# schematic.net
KiCad netlist of a schematic drawn in EasyEDA
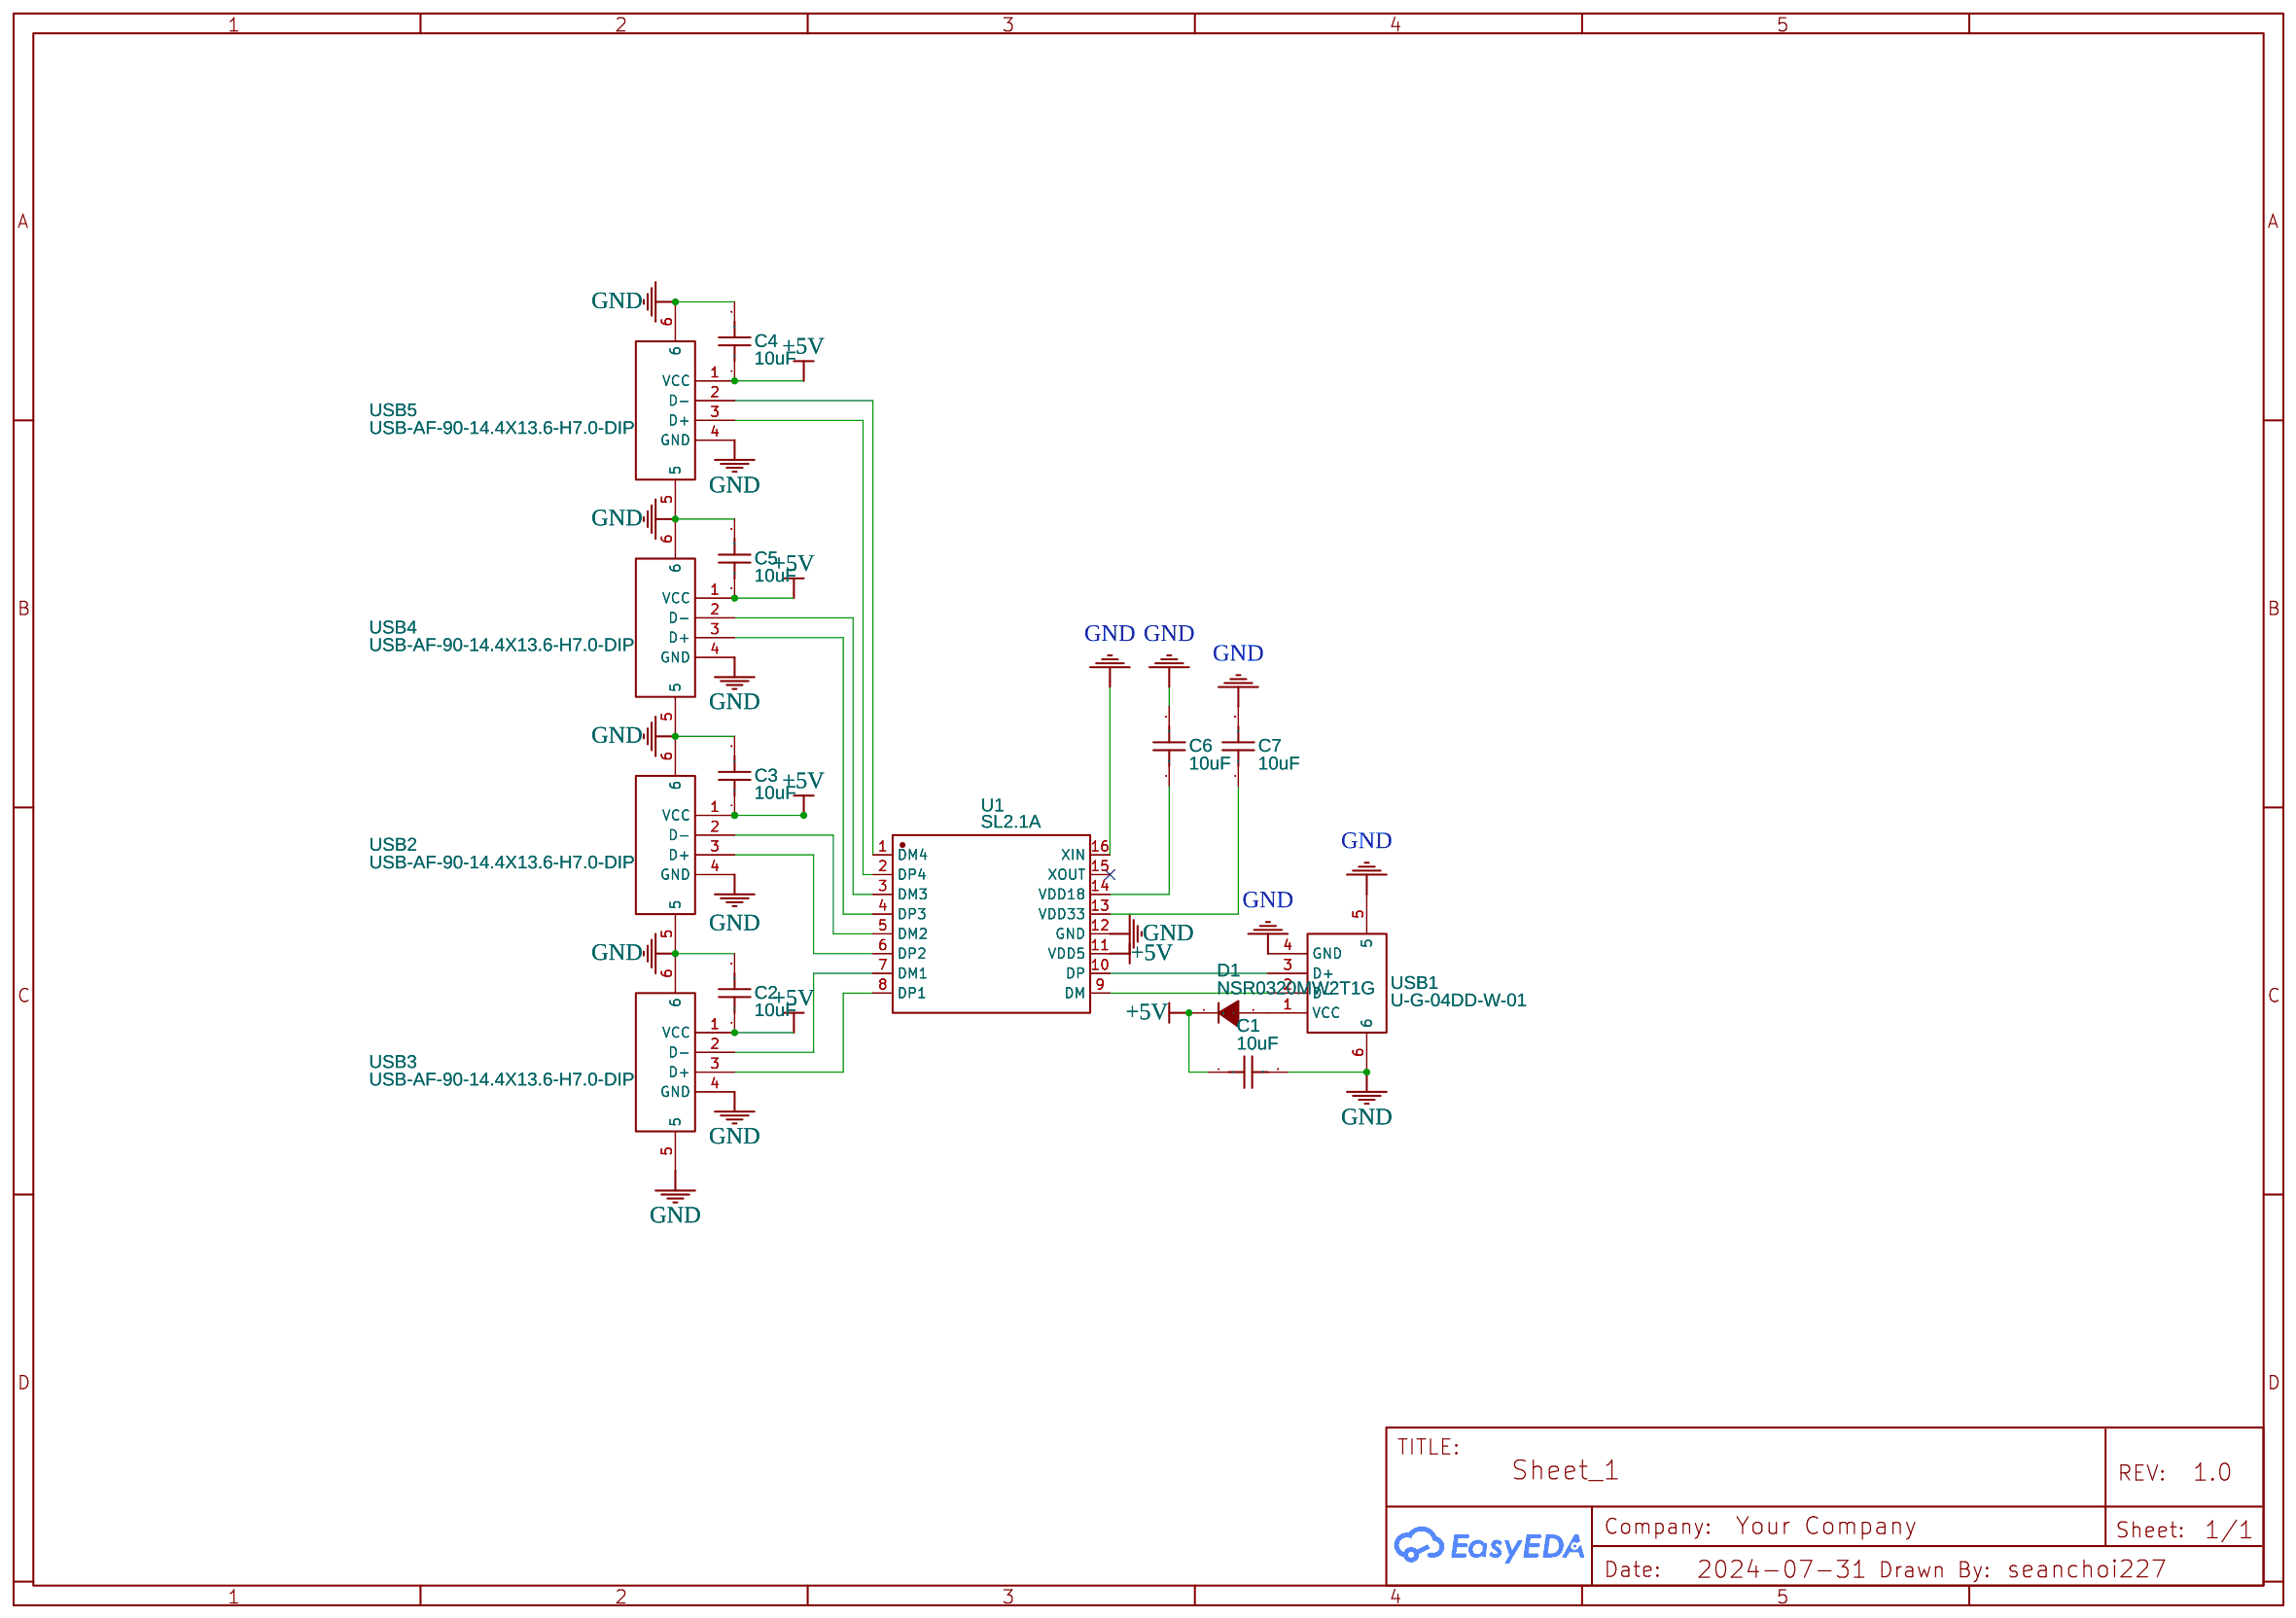
[diagram p0: schematic sheet]

(export (version "E")
  (design (tool "Eeschema 10.0.6"))
  (components
    (comp (ref "C1")
      (value "10uF")
      (fields
        (field (name "Manufacturer Part") "CL10A106KP8NNNC")
        (field (name "Manufacturer") "SAMSUNG(三星)")
      )
      (libsource (lib "") (part "CL10A106KP8NNNC_1"))
    )
    (comp (ref "C2")
      (value "10uF")
      (fields
        (field (name "Manufacturer Part") "CL10A106KP8NNNC")
        (field (name "Manufacturer") "SAMSUNG(三星)")
      )
      (libsource (lib "") (part "CL10A106KP8NNNC"))
    )
    (comp (ref "C3")
      (value "10uF")
      (fields
        (field (name "Manufacturer Part") "CL10A106KP8NNNC")
        (field (name "Manufacturer") "SAMSUNG(三星)")
      )
      (libsource (lib "") (part "CL10A106KP8NNNC"))
    )
    (comp (ref "C4")
      (value "10uF")
      (fields
        (field (name "Manufacturer Part") "CL10A106KP8NNNC")
        (field (name "Manufacturer") "SAMSUNG(三星)")
      )
      (libsource (lib "") (part "CL10A106KP8NNNC"))
    )
    (comp (ref "C5")
      (value "10uF")
      (fields
        (field (name "Manufacturer Part") "CL10A106KP8NNNC")
        (field (name "Manufacturer") "SAMSUNG(三星)")
      )
      (libsource (lib "") (part "CL10A106KP8NNNC"))
    )
    (comp (ref "C6")
      (value "10uF")
      (fields
        (field (name "Manufacturer Part") "CL10A106KP8NNNC")
        (field (name "Manufacturer") "SAMSUNG(三星)")
      )
      (libsource (lib "") (part "CL10A106KP8NNNC"))
    )
    (comp (ref "C7")
      (value "10uF")
      (fields
        (field (name "Manufacturer Part") "CL10A106KP8NNNC")
        (field (name "Manufacturer") "SAMSUNG(三星)")
      )
      (libsource (lib "") (part "CL10A106KP8NNNC"))
    )
    (comp (ref "D1")
      (value "NSR0320MW2T1G")
      (fields (field (name "Manufacturer") "onsemi(安森美)"))
      (libsource (lib "") (part "NSR0320MW2T1G"))
    )
    (comp (ref "U1")
      (value "SL2.1A")
      (fields (field (name "Manufacturer") "CoreChips(和芯润德)"))
      (libsource (lib "") (part "SL2.1A"))
    )
    (comp (ref "USB1")
      (value "U-G-04DD-W-01")
      (fields (field (name "Manufacturer Part") "U-G-O4DD-W-1") (field (name "Manufacturer") "韩国韩荣"))
      (libsource (lib "") (part "U-G-04DD-W-01"))
    )
    (comp (ref "USB2")
      (value "USB-AF-90-14.4X13.6-H7.0-DIP")
      (fields (field (name "Manufacturer Part") "903-131A1011D10100") (field (name "Manufacturer") "精拓金"))
      (libsource (lib "") (part "USB-AF-90-14.4X13.6-H7.0-DIP"))
    )
    (comp (ref "USB3")
      (value "USB-AF-90-14.4X13.6-H7.0-DIP")
      (fields (field (name "Manufacturer Part") "903-131A1011D10100") (field (name "Manufacturer") "精拓金"))
      (libsource (lib "") (part "USB-AF-90-14.4X13.6-H7.0-DIP"))
    )
    (comp (ref "USB4")
      (value "USB-AF-90-14.4X13.6-H7.0-DIP")
      (fields (field (name "Manufacturer Part") "903-131A1011D10100") (field (name "Manufacturer") "精拓金"))
      (libsource (lib "") (part "USB-AF-90-14.4X13.6-H7.0-DIP"))
    )
    (comp (ref "USB5")
      (value "USB-AF-90-14.4X13.6-H7.0-DIP")
      (fields (field (name "Manufacturer Part") "903-131A1011D10100") (field (name "Manufacturer") "精拓金"))
      (libsource (lib "") (part "USB-AF-90-14.4X13.6-H7.0-DIP"))
    )
  )
  (nets
    (net (code "1") (name "+5V") (class "Default")
      (node (ref "C1") (pin "1") (pinfunction "1_1") (pintype "unspecified"))
      (node (ref "C2") (pin "1") (pinfunction "1_1") (pintype "unspecified"))
      (node (ref "C3") (pin "1") (pinfunction "1_1") (pintype "unspecified"))
      (node (ref "C4") (pin "1") (pinfunction "1_1") (pintype "unspecified"))
      (node (ref "C5") (pin "1") (pinfunction "1_1") (pintype "unspecified"))
      (node (ref "D1") (pin "1") (pinfunction "C_1") (pintype "unspecified"))
      (node (ref "U1") (pin "11") (pinfunction "VDD5_11") (pintype "unspecified"))
      (node (ref "USB2") (pin "1") (pinfunction "VCC_1") (pintype "unspecified"))
      (node (ref "USB3") (pin "1") (pinfunction "VCC_1") (pintype "unspecified"))
      (node (ref "USB4") (pin "1") (pinfunction "VCC_1") (pintype "unspecified"))
      (node (ref "USB5") (pin "1") (pinfunction "VCC_1") (pintype "unspecified"))
    )
    (net (code "2") (name "GND") (class "Default")
      (node (ref "C1") (pin "2") (pinfunction "2_2") (pintype "unspecified"))
      (node (ref "C2") (pin "2") (pinfunction "2_2") (pintype "unspecified"))
      (node (ref "C3") (pin "2") (pinfunction "2_2") (pintype "unspecified"))
      (node (ref "C4") (pin "2") (pinfunction "2_2") (pintype "unspecified"))
      (node (ref "C5") (pin "2") (pinfunction "2_2") (pintype "unspecified"))
      (node (ref "C6") (pin "2") (pinfunction "2_2") (pintype "unspecified"))
      (node (ref "C7") (pin "2") (pinfunction "2_2") (pintype "unspecified"))
      (node (ref "U1") (pin "12") (pinfunction "GND_12") (pintype "unspecified"))
      (node (ref "U1") (pin "16") (pinfunction "XIN_16") (pintype "unspecified"))
      (node (ref "USB1") (pin "4") (pinfunction "GND_4") (pintype "unspecified"))
      (node (ref "USB1") (pin "5") (pinfunction "5_5") (pintype "unspecified"))
      (node (ref "USB1") (pin "6") (pinfunction "6_6") (pintype "unspecified"))
      (node (ref "USB2") (pin "4") (pinfunction "GND_4") (pintype "unspecified"))
      (node (ref "USB2") (pin "5") (pinfunction "5_5") (pintype "unspecified"))
      (node (ref "USB2") (pin "6") (pinfunction "6_6") (pintype "unspecified"))
      (node (ref "USB3") (pin "4") (pinfunction "GND_4") (pintype "unspecified"))
      (node (ref "USB3") (pin "5") (pinfunction "5_5") (pintype "unspecified"))
      (node (ref "USB3") (pin "6") (pinfunction "6_6") (pintype "unspecified"))
      (node (ref "USB4") (pin "4") (pinfunction "GND_4") (pintype "unspecified"))
      (node (ref "USB4") (pin "5") (pinfunction "5_5") (pintype "unspecified"))
      (node (ref "USB4") (pin "6") (pinfunction "6_6") (pintype "unspecified"))
      (node (ref "USB5") (pin "4") (pinfunction "GND_4") (pintype "unspecified"))
      (node (ref "USB5") (pin "5") (pinfunction "5_5") (pintype "unspecified"))
      (node (ref "USB5") (pin "6") (pinfunction "6_6") (pintype "unspecified"))
    )
    (net (code "3") (name "Net-(D1-A)") (class "Default")
      (node (ref "D1") (pin "2") (pinfunction "A_2") (pintype "unspecified"))
      (node (ref "USB1") (pin "1") (pinfunction "VCC_1") (pintype "unspecified"))
    )
    (net (code "4") (name "Net-(U1-DM)") (class "Default")
      (node (ref "U1") (pin "9") (pinfunction "DM_9") (pintype "unspecified"))
      (node (ref "USB1") (pin "2") (pinfunction "D-_2") (pintype "unspecified"))
    )
    (net (code "5") (name "Net-(U1-DM1)") (class "Default")
      (node (ref "U1") (pin "7") (pinfunction "DM1_7") (pintype "unspecified"))
      (node (ref "USB3") (pin "2") (pinfunction "D-_2") (pintype "unspecified"))
    )
    (net (code "6") (name "Net-(U1-DM2)") (class "Default")
      (node (ref "U1") (pin "5") (pinfunction "DM2_5") (pintype "unspecified"))
      (node (ref "USB2") (pin "2") (pinfunction "D-_2") (pintype "unspecified"))
    )
    (net (code "7") (name "Net-(U1-DM3)") (class "Default")
      (node (ref "U1") (pin "3") (pinfunction "DM3_3") (pintype "unspecified"))
      (node (ref "USB4") (pin "2") (pinfunction "D-_2") (pintype "unspecified"))
    )
    (net (code "8") (name "Net-(U1-DM4)") (class "Default")
      (node (ref "U1") (pin "1") (pinfunction "DM4_1") (pintype "unspecified"))
      (node (ref "USB5") (pin "2") (pinfunction "D-_2") (pintype "unspecified"))
    )
    (net (code "9") (name "Net-(U1-DP)") (class "Default")
      (node (ref "U1") (pin "10") (pinfunction "DP_10") (pintype "unspecified"))
      (node (ref "USB1") (pin "3") (pinfunction "D+_3") (pintype "unspecified"))
    )
    (net (code "10") (name "Net-(U1-DP1)") (class "Default")
      (node (ref "U1") (pin "8") (pinfunction "DP1_8") (pintype "unspecified"))
      (node (ref "USB3") (pin "3") (pinfunction "D+_3") (pintype "unspecified"))
    )
    (net (code "11") (name "Net-(U1-DP2)") (class "Default")
      (node (ref "U1") (pin "6") (pinfunction "DP2_6") (pintype "unspecified"))
      (node (ref "USB2") (pin "3") (pinfunction "D+_3") (pintype "unspecified"))
    )
    (net (code "12") (name "Net-(U1-DP3)") (class "Default")
      (node (ref "U1") (pin "4") (pinfunction "DP3_4") (pintype "unspecified"))
      (node (ref "USB4") (pin "3") (pinfunction "D+_3") (pintype "unspecified"))
    )
    (net (code "13") (name "Net-(U1-DP4)") (class "Default")
      (node (ref "U1") (pin "2") (pinfunction "DP4_2") (pintype "unspecified"))
      (node (ref "USB5") (pin "3") (pinfunction "D+_3") (pintype "unspecified"))
    )
    (net (code "14") (name "Net-(U1-VDD18)") (class "Default")
      (node (ref "C6") (pin "1") (pinfunction "1_1") (pintype "unspecified"))
      (node (ref "U1") (pin "14") (pinfunction "VDD18_14") (pintype "unspecified"))
    )
    (net (code "15") (name "Net-(U1-VDD33)") (class "Default")
      (node (ref "C7") (pin "1") (pinfunction "1_1") (pintype "unspecified"))
      (node (ref "U1") (pin "13") (pinfunction "VDD33_13") (pintype "unspecified"))
    )
    (net (code "16") (name "unconnected-(U1-XOUT-Pad15)") (class "Default")
      (node (ref "U1") (pin "15") (pinfunction "XOUT_15") (pintype "unspecified+no_connect"))
    )
  )
)
